# SHDN-S06-V00-IsolatedCAN.net
KiCad netlist of a schematic drawn in Altium Designer
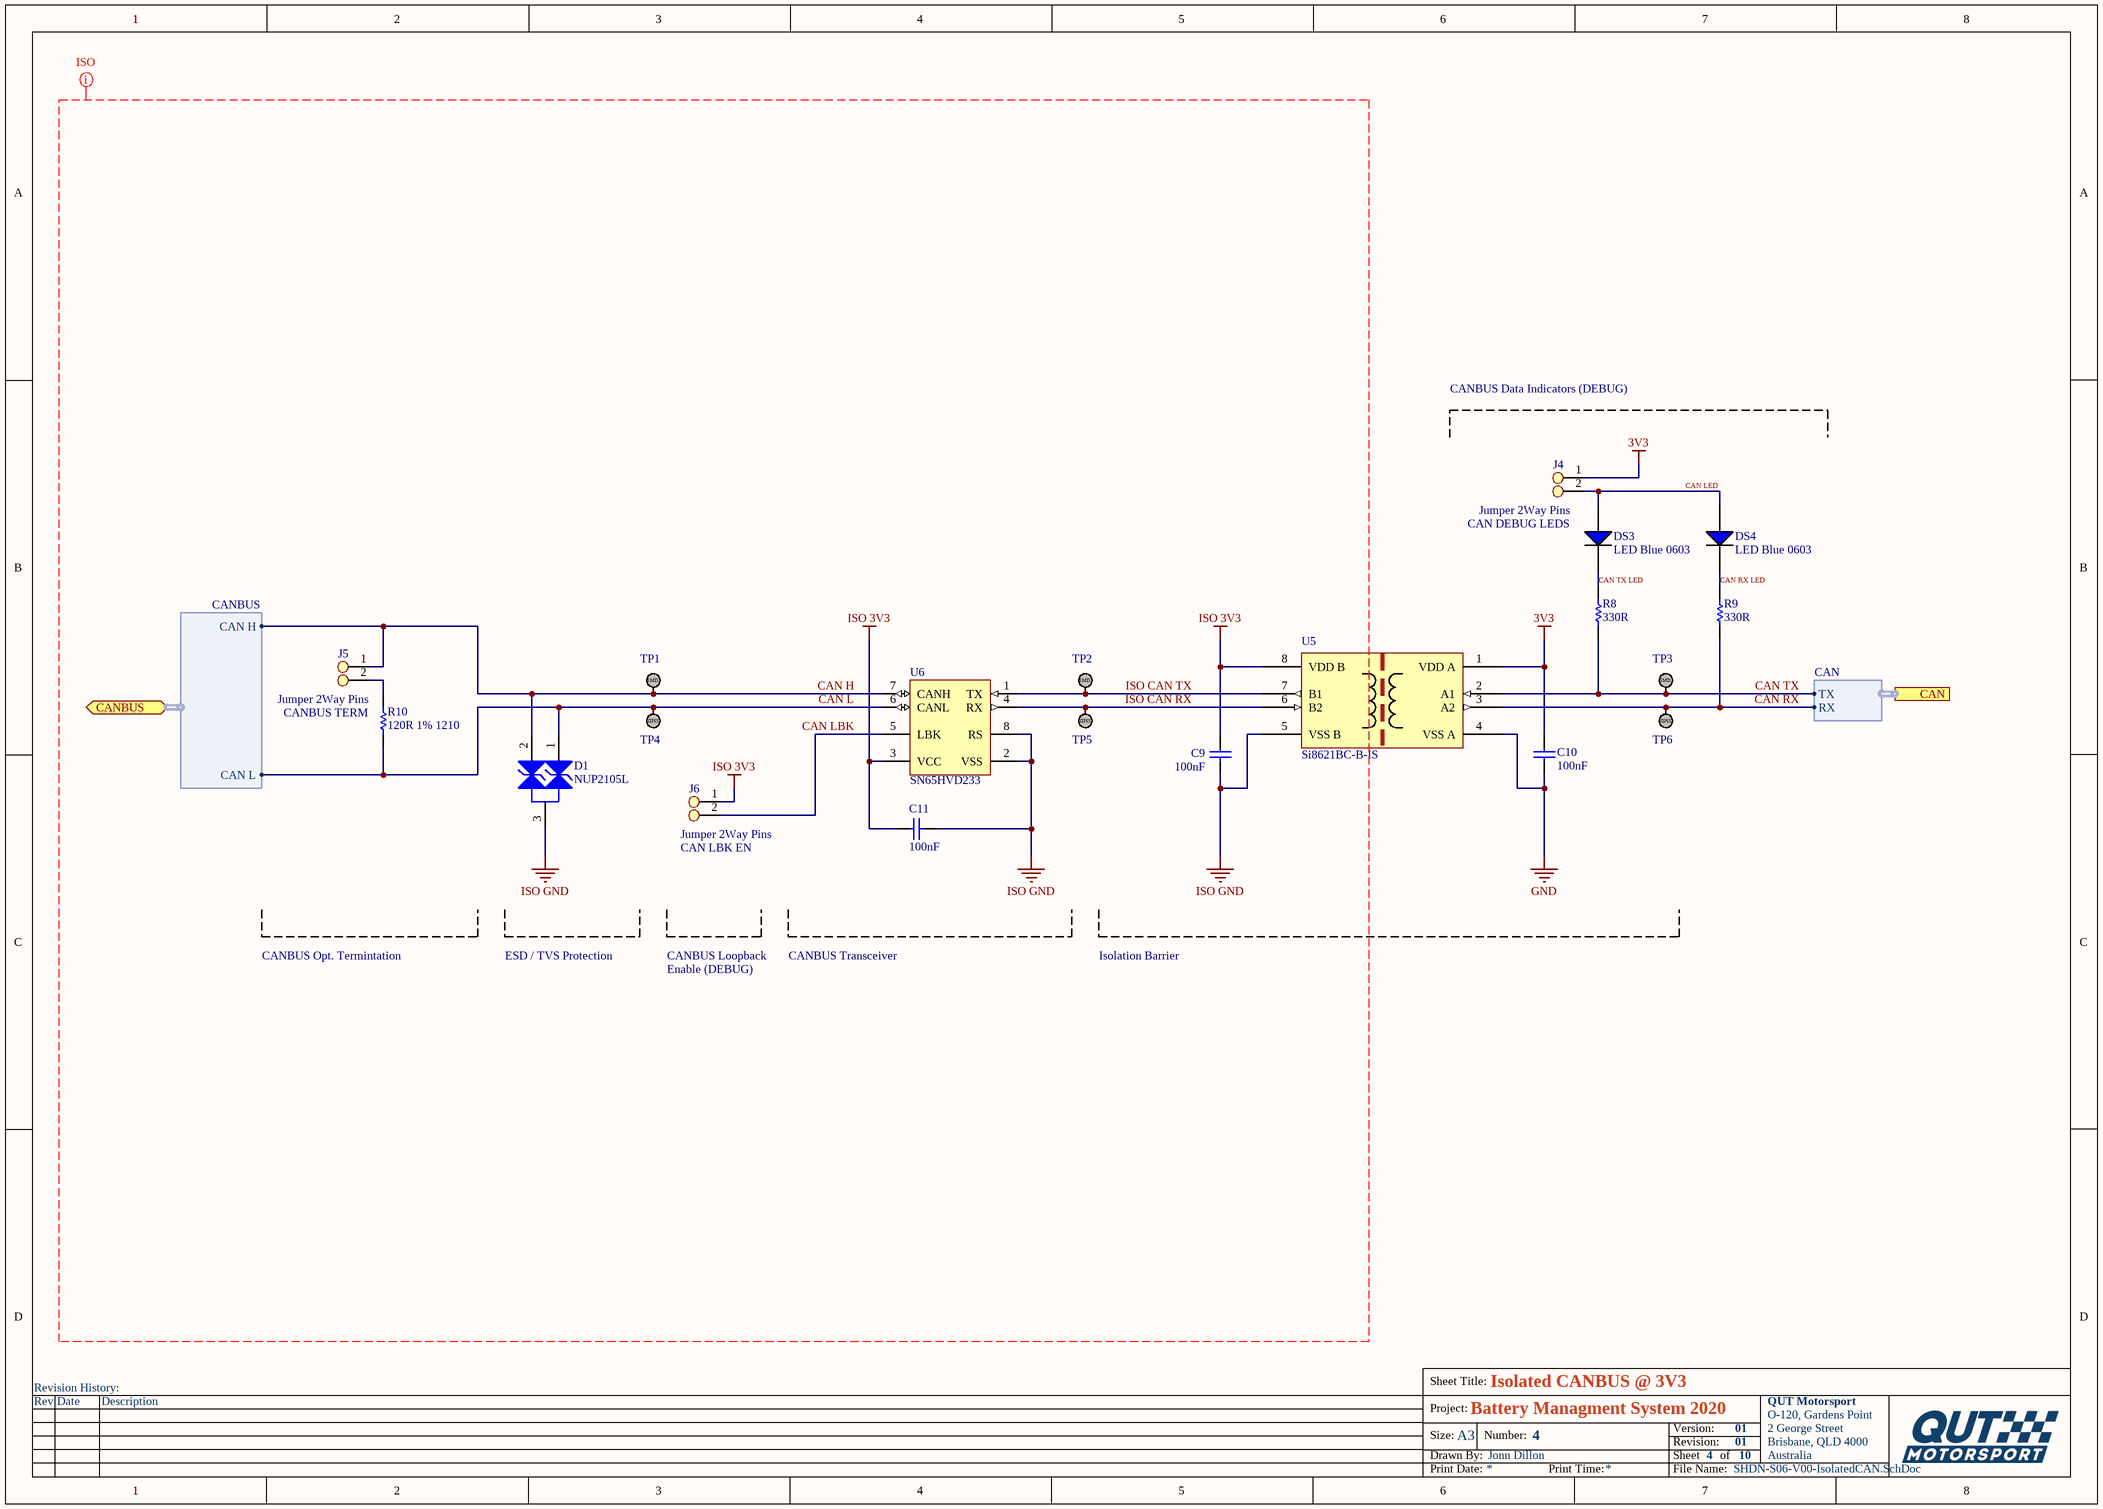
[diagram p0: SHDN-S06-V00-IsolatedCAN.SchDoc]

(export (version "E")
  (design (tool "Eeschema 10.0.6"))
  (components
    (comp (ref "C9")
      (value "100nF")
      (footprint "Cap_Ceramic_0603")
      (description "Capacitor, Ceramic, SMD, 100nF, 50V, 5%, X7R, 0603")
      (libsource (lib "StandardCapacitors") (part "100nF 50V 5% X7R 0603"))
    )
    (comp (ref "C10")
      (value "100nF")
      (footprint "Cap_Ceramic_0603")
      (description "Capacitor, Ceramic, SMD, 100nF, 50V, 5%, X7R, 0603")
      (libsource (lib "StandardCapacitors") (part "100nF 50V 5% X7R 0603"))
    )
    (comp (ref "C11")
      (value "100nF")
      (footprint "Cap_Ceramic_0603")
      (description "Capacitor, Ceramic, SMD, 100nF, 50V, 5%, X7R, 0603")
      (libsource (lib "StandardCapacitors") (part "100nF 50V 5% X7R 0603"))
    )
    (comp (ref "D1")
      (value "NUP2105L")
      (footprint "NUP2105L")
      (libsource (lib "QUTMS_CANLibrary") (part "NUP2105L"))
    )
    (comp (ref "DS3")
      (value "LED Blue 0603")
      (footprint "LED BLUE 0603")
      (libsource (lib "QUTMS_LEDLibrary") (part "LED BLUE 0603"))
    )
    (comp (ref "DS4")
      (value "LED Blue 0603")
      (footprint "LED BLUE 0603")
      (libsource (lib "QUTMS_LEDLibrary") (part "LED BLUE 0603"))
    )
    (comp (ref "J4")
      (value "Jumper 2Way Pins")
      (footprint "Jumper_2Way_Pin")
      (description "Jumper 2Way Side Pins")
      (libsource (lib "QUTMS_JumperLibrary") (part "Jumper 2Way Side Pins"))
    )
    (comp (ref "J5")
      (value "Jumper 2Way Pins")
      (footprint "Jumper_2Way_Pin")
      (description "Jumper 2Way Side Pins")
      (libsource (lib "QUTMS_JumperLibrary") (part "Jumper 2Way Side Pins"))
    )
    (comp (ref "J6")
      (value "Jumper 2Way Pins")
      (footprint "Jumper_2Way_Pin")
      (description "Jumper 2Way Side Pins")
      (libsource (lib "QUTMS_JumperLibrary") (part "Jumper 2Way Side Pins"))
    )
    (comp (ref "R8")
      (value "330R")
      (footprint "Res_ThinFilm_0603")
      (description "Resistor, SMD, 330R, 0.1W, 5%, 0603")
      (libsource (lib "StandardResistors") (part "330R 5% 0603"))
    )
    (comp (ref "R9")
      (value "330R")
      (footprint "Res_ThinFilm_0603")
      (description "Resistor, SMD, 330R, 0.1W, 5%, 0603")
      (libsource (lib "StandardResistors") (part "330R 5% 0603"))
    )
    (comp (ref "R10")
      (value "120R 1% 1210")
      (footprint "Res_ThinFilm_1210")
      (description "Resistor, SMD, 120R, 0.25W, 1%, 1210")
      (libsource (lib "StandardResistors") (part "120R 1% 1210"))
    )
    (comp (ref "TP1")
      (value "TestPoint_SMD")
      (footprint "TestPointSMD")
      (libsource (lib "StandardTest") (part "TestPoint_SMD"))
    )
    (comp (ref "TP2")
      (value "TestPoint_SMD")
      (footprint "TestPointSMD")
      (libsource (lib "StandardTest") (part "TestPoint_SMD"))
    )
    (comp (ref "TP3")
      (value "TestPoint_SMD")
      (footprint "TestPointSMD")
      (libsource (lib "StandardTest") (part "TestPoint_SMD"))
    )
    (comp (ref "TP4")
      (value "TestPoint_SMD")
      (footprint "TestPointSMD")
      (libsource (lib "StandardTest") (part "TestPoint_SMD"))
    )
    (comp (ref "TP5")
      (value "TestPoint_SMD")
      (footprint "TestPointSMD")
      (libsource (lib "StandardTest") (part "TestPoint_SMD"))
    )
    (comp (ref "TP6")
      (value "TestPoint_SMD")
      (footprint "TestPointSMD")
      (libsource (lib "StandardTest") (part "TestPoint_SMD"))
    )
    (comp (ref "U5")
      (value "Si8621BC-B-IS")
      (footprint "Si8621BC-B-IS")
      (libsource (lib "QUTMS_IsolatorLibrary") (part "Si8621BC-B-IS"))
    )
    (comp (ref "U6")
      (value "SN65HVD233")
      (footprint "SN65HVD233DR")
      (libsource (lib "QUTMS_CANLibrary") (part "SN65HVD233"))
    )
  )
  (nets
    (net (code "3") (name "/CAN H") (class "Default")
      (node (ref "D1") (pin "2") (pinfunction "2_2") (pintype "passive"))
      (node (ref "J5") (pin "1") (pinfunction "1_1") (pintype "passive"))
      (node (ref "TP1") (pin "1") (pinfunction "1_1") (pintype "passive"))
      (node (ref "U6") (pin "7") (pinfunction "CANH_7") (pintype "bidirectional"))
    )
    (net (code "4") (name "/CAN L") (class "Default")
      (node (ref "D1") (pin "1") (pinfunction "1_1") (pintype "passive"))
      (node (ref "R10") (pin "1") (pinfunction "1_1") (pintype "passive"))
      (node (ref "TP4") (pin "1") (pinfunction "1_1") (pintype "passive"))
      (node (ref "U6") (pin "6") (pinfunction "CANL_6") (pintype "bidirectional"))
    )
    (net (code "5") (name "/CAN LBK") (class "Default")
      (node (ref "J6") (pin "2") (pinfunction "2_2") (pintype "passive"))
      (node (ref "U6") (pin "5") (pinfunction "LBK_5") (pintype "passive"))
    )
    (net (code "6") (name "/CAN LED") (class "Default")
      (node (ref "DS3") (pin "1") (pinfunction "A_1") (pintype "passive"))
      (node (ref "DS4") (pin "1") (pinfunction "A_1") (pintype "passive"))
      (node (ref "J4") (pin "2") (pinfunction "2_2") (pintype "passive"))
    )
    (net (code "7") (name "/CAN RX") (class "Default")
      (node (ref "R9") (pin "1") (pinfunction "1_1") (pintype "passive"))
      (node (ref "TP6") (pin "1") (pinfunction "1_1") (pintype "passive"))
      (node (ref "U5") (pin "3") (pinfunction "A2_3") (pintype "output"))
    )
    (net (code "8") (name "/CAN RX LED") (class "Default")
      (node (ref "DS4") (pin "2") (pinfunction "C_2") (pintype "passive"))
      (node (ref "R9") (pin "2") (pinfunction "2_2") (pintype "passive"))
    )
    (net (code "9") (name "/CAN TX") (class "Default")
      (node (ref "R8") (pin "1") (pinfunction "1_1") (pintype "passive"))
      (node (ref "TP3") (pin "1") (pinfunction "1_1") (pintype "passive"))
      (node (ref "U5") (pin "2") (pinfunction "A1_2") (pintype "input"))
    )
    (net (code "10") (name "/CAN TX LED") (class "Default")
      (node (ref "DS3") (pin "2") (pinfunction "C_2") (pintype "passive"))
      (node (ref "R8") (pin "2") (pinfunction "2_2") (pintype "passive"))
    )
    (net (code "11") (name "/ISO CAN RX") (class "Default")
      (node (ref "TP5") (pin "1") (pinfunction "1_1") (pintype "passive"))
      (node (ref "U5") (pin "6") (pinfunction "B2_6") (pintype "input"))
      (node (ref "U6") (pin "4") (pinfunction "RX_4") (pintype "output"))
    )
    (net (code "12") (name "/ISO CAN TX") (class "Default")
      (node (ref "TP2") (pin "1") (pinfunction "1_1") (pintype "passive"))
      (node (ref "U5") (pin "7") (pinfunction "B1_7") (pintype "output"))
      (node (ref "U6") (pin "1") (pinfunction "TX_1") (pintype "input"))
    )
    (net (code "15") (name "3V3") (class "Default")
      (node (ref "C10") (pin "2") (pinfunction "2_2") (pintype "passive"))
      (node (ref "J4") (pin "1") (pinfunction "1_1") (pintype "passive"))
      (node (ref "U5") (pin "1") (pinfunction "VDD_A_1") (pintype "passive"))
    )
    (net (code "16") (name "GND") (class "Default")
      (node (ref "C10") (pin "1") (pinfunction "1_1") (pintype "passive"))
      (node (ref "U5") (pin "4") (pinfunction "VSS_A_4") (pintype "passive"))
    )
    (net (code "17") (name "ISO 3V3") (class "Default")
      (node (ref "C11") (pin "2") (pinfunction "2_2") (pintype "passive"))
      (node (ref "C9") (pin "2") (pinfunction "2_2") (pintype "passive"))
      (node (ref "J6") (pin "1") (pinfunction "1_1") (pintype "passive"))
      (node (ref "U5") (pin "8") (pinfunction "VDD_B_8") (pintype "passive"))
      (node (ref "U6") (pin "3") (pinfunction "VCC_3") (pintype "passive"))
    )
    (net (code "18") (name "ISO GND") (class "Default")
      (node (ref "C11") (pin "1") (pinfunction "1_1") (pintype "passive"))
      (node (ref "C9") (pin "1") (pinfunction "1_1") (pintype "passive"))
      (node (ref "D1") (pin "3") (pinfunction "3_3") (pintype "passive"))
      (node (ref "U5") (pin "5") (pinfunction "VSS_B_5") (pintype "passive"))
      (node (ref "U6") (pin "2") (pinfunction "VSS_2") (pintype "passive"))
      (node (ref "U6") (pin "8") (pinfunction "RS_8") (pintype "passive"))
    )
    (net (code "19") (name "Net-(J5-Pad2)") (class "Default")
      (node (ref "J5") (pin "2") (pinfunction "2_2") (pintype "passive"))
      (node (ref "R10") (pin "2") (pinfunction "2_2") (pintype "passive"))
    )
  )
)
